# POWER.net
KiCad netlist of a schematic drawn in Altium Designer
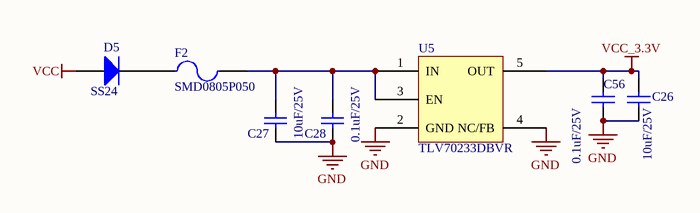
[diagram p0: POWER.SchDoc]

(export (version "E")
  (design (tool "Eeschema 10.0.6"))
  (components
    (comp (ref "C26")
      (value "10uF/25V")
      (footprint "0603C")
      (description "Capacitor")
      (fields (field (name "PUBLISHER") "Altium Limited"))
      (libsource (lib "Miscellaneous Devices") (part "Cap"))
    )
    (comp (ref "C27")
      (value "10uF/25V")
      (footprint "0603C")
      (description "Capacitor")
      (fields (field (name "PUBLISHER") "Altium Limited"))
      (libsource (lib "Miscellaneous Devices") (part "Cap"))
    )
    (comp (ref "C28")
      (value "0.1uF/25V")
      (footprint "0603C")
      (description "Capacitor")
      (fields (field (name "PUBLISHER") "Altium Limited"))
      (libsource (lib "Miscellaneous Devices") (part "Cap"))
    )
    (comp (ref "C56")
      (value "0.1uF/25V")
      (footprint "0603C")
      (description "Capacitor")
      (fields (field (name "PUBLISHER") "Altium Limited"))
      (libsource (lib "Miscellaneous Devices") (part "Cap"))
    )
    (comp (ref "D5")
      (value "SS24")
      (footprint "SMA")
      (description "High Conductance Fast Diode")
      (fields (field (name "PUBLISHER") "Altium Limited"))
      (libsource (lib "Miscellaneous Devices") (part "Diode 1N4148"))
    )
    (comp (ref "F2")
      (value "SMD0805P050")
      (footprint "0805R")
      (description "Fuse")
      (fields (field (name "PUBLISHER") "Altium Limited"))
      (libsource (lib "Miscellaneous Devices") (part "Fuse 2"))
    )
    (comp (ref "U5")
      (value "TLV70233DBVR")
      (footprint "SOT23-5(DBV)")
      (libsource (lib "Schlib_20110825") (part "TLV70230DBVR"))
    )
  )
  (nets
    (net (code "1") (name "GND") (class "Default")
      (node (ref "C26") (pin "1") (pinfunction "1_1") (pintype "passive"))
      (node (ref "C27") (pin "1") (pinfunction "1_1") (pintype "passive"))
      (node (ref "C28") (pin "2") (pinfunction "2_2") (pintype "passive"))
      (node (ref "C56") (pin "2") (pinfunction "2_2") (pintype "passive"))
      (node (ref "U5") (pin "2") (pinfunction "GND_2") (pintype "passive"))
      (node (ref "U5") (pin "4") (pinfunction "NC/FB_4") (pintype "passive"))
    )
    (net (code "2") (name "Net-(D5-K)") (class "Default")
      (node (ref "D5") (pin "2") (pinfunction "K_2") (pintype "passive"))
      (node (ref "F2") (pin "1") (pinfunction "1_1") (pintype "passive"))
    )
    (net (code "3") (name "Net-(U5-EN)") (class "Default")
      (node (ref "C27") (pin "2") (pinfunction "2_2") (pintype "passive"))
      (node (ref "C28") (pin "1") (pinfunction "1_1") (pintype "passive"))
      (node (ref "F2") (pin "2") (pinfunction "2_2") (pintype "passive"))
      (node (ref "U5") (pin "1") (pinfunction "IN_1") (pintype "passive"))
      (node (ref "U5") (pin "3") (pinfunction "EN_3") (pintype "passive"))
    )
    (net (code "4") (name "VCC") (class "Default")
      (node (ref "D5") (pin "1") (pinfunction "A_1") (pintype "passive"))
    )
    (net (code "5") (name "VCC_3.3V") (class "Default")
      (node (ref "C26") (pin "2") (pinfunction "2_2") (pintype "passive"))
      (node (ref "C56") (pin "1") (pinfunction "1_1") (pintype "passive"))
      (node (ref "U5") (pin "5") (pinfunction "OUT_5") (pintype "passive"))
    )
  )
)
